# 5VBuck_MP2236_P1.net
KiCad netlist of a schematic drawn in EasyEDA Pro
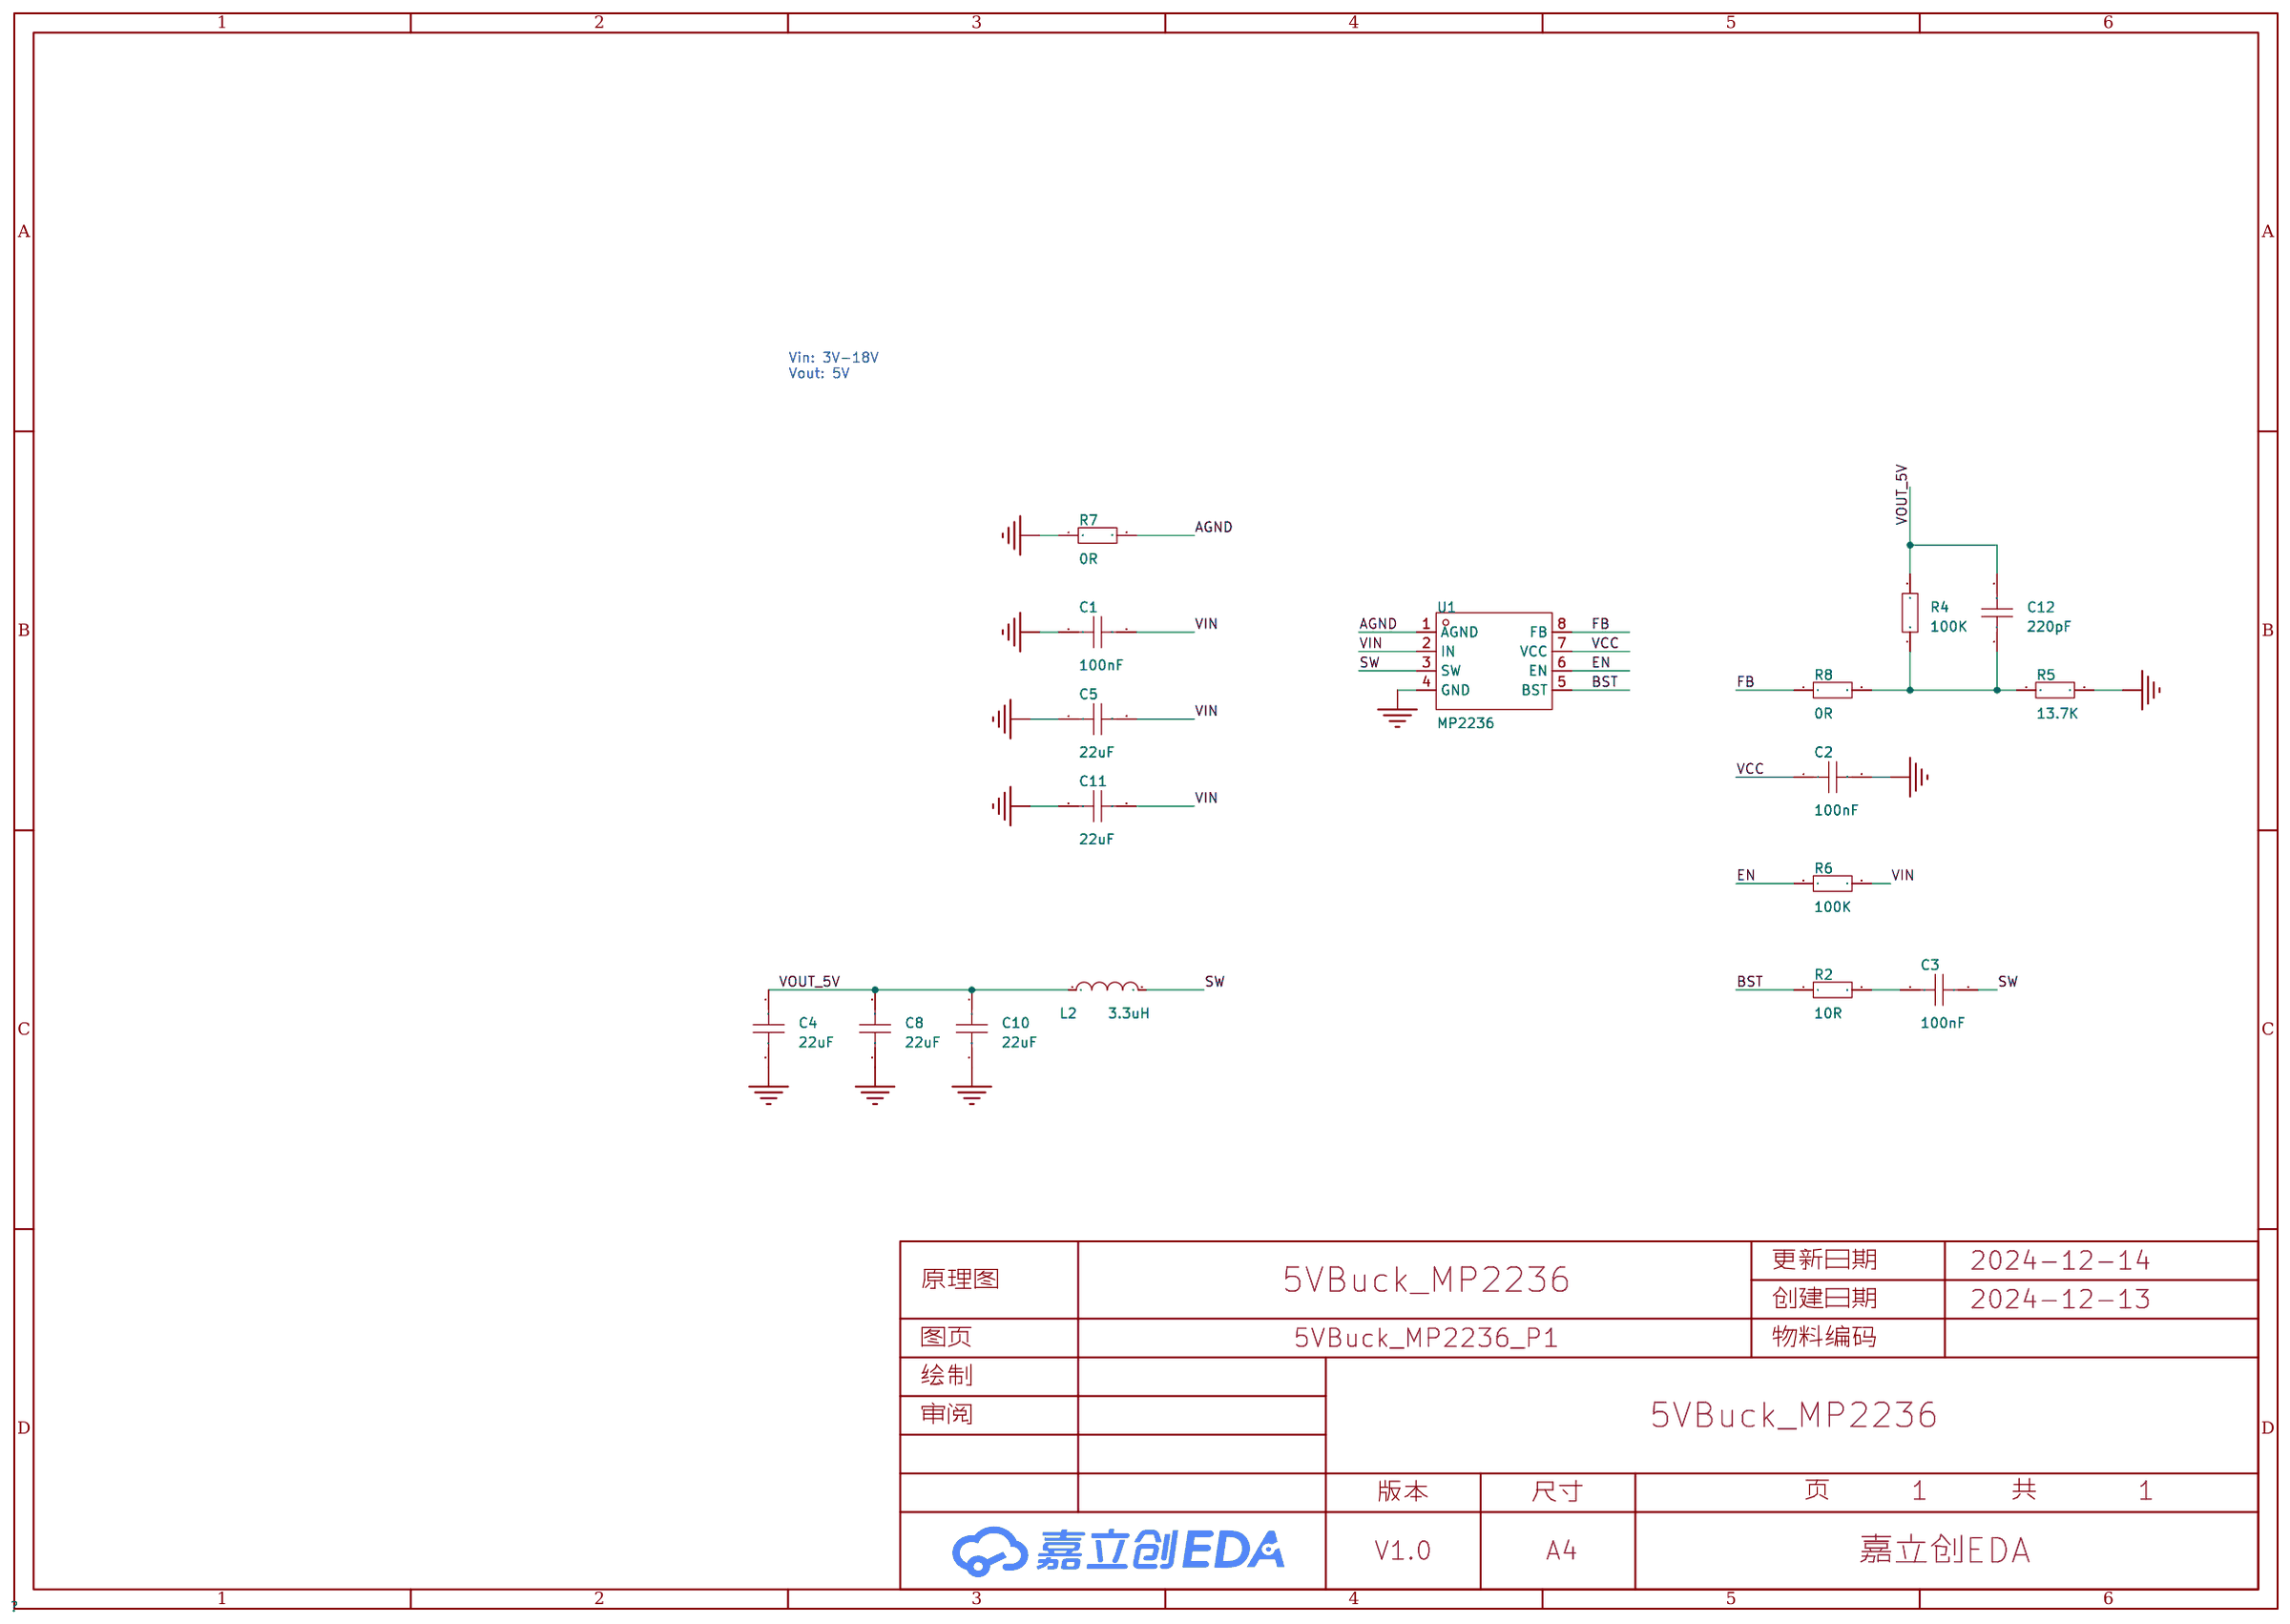
[diagram p0: schematic sheet]

(export (version "E")
  (design (tool "Eeschema 10.0.6"))
  (components
    (comp (ref "C1")
      (value "100nF")
      (footprint "easyedapro:C0805")
      (libsource (lib "easyedapro") (part "CapAcitance"))
    )
    (comp (ref "C2")
      (value "100nF")
      (footprint "easyedapro:C0805")
      (libsource (lib "easyedapro") (part "CapAcitance"))
    )
    (comp (ref "C3")
      (value "100nF")
      (footprint "easyedapro:C0805")
      (libsource (lib "easyedapro") (part "CapAcitance"))
    )
    (comp (ref "C4")
      (value "22uF")
      (footprint "easyedapro:C0805")
      (libsource (lib "easyedapro") (part "CapAcitance"))
    )
    (comp (ref "C5")
      (value "22uF")
      (footprint "easyedapro:C0805")
      (libsource (lib "easyedapro") (part "CapAcitance"))
    )
    (comp (ref "C8")
      (value "22uF")
      (footprint "easyedapro:C0805")
      (libsource (lib "easyedapro") (part "CapAcitance"))
    )
    (comp (ref "C10")
      (value "22uF")
      (footprint "easyedapro:C0805")
      (libsource (lib "easyedapro") (part "CapAcitance"))
    )
    (comp (ref "C11")
      (value "22uF")
      (footprint "easyedapro:C0805")
      (libsource (lib "easyedapro") (part "CapAcitance"))
    )
    (comp (ref "C12")
      (value "220pF")
      (footprint "easyedapro:C0805")
      (libsource (lib "easyedapro") (part "CapAcitance"))
    )
    (comp (ref "L2")
      (value "3.3uH")
      (footprint "easyedapro:IND-SMD_L7.1-W6.6_MJC-0603T")
      (description "电感值:5.6uH;精度:±20%;额定电流:5.5A;饱和电流(Isat):7A;类型:一体成型电感;")
      (fields
        (field (name "Manufacturer Part") "CXP0630-5R6M-AG(5.6uh)")
        (field (name "Manufacturer") "DMBJ(振宝佳)")
      )
      (libsource (lib "easyedapro") (part "CXP0630-5R6M-AG(5.6UH)"))
    )
    (comp (ref "R2") (value "10R") (footprint "easyedapro:R0805") (libsource (lib "easyedapro") (part "电阻")))
    (comp (ref "R4") (value "100K") (footprint "easyedapro:R0805") (libsource (lib "easyedapro") (part "电阻")))
    (comp (ref "R5")
      (value "13.7K")
      (footprint "easyedapro:R0805")
      (libsource (lib "easyedapro") (part "电阻"))
    )
    (comp (ref "R6") (value "100K") (footprint "easyedapro:R0805") (libsource (lib "easyedapro") (part "电阻")))
    (comp (ref "R7") (value "0R") (footprint "easyedapro:R0805") (libsource (lib "easyedapro") (part "电阻")))
    (comp (ref "R8") (value "0R") (footprint "easyedapro:R0805") (libsource (lib "easyedapro") (part "电阻")))
    (comp (ref "U1")
      (value "MP2236")
      (footprint "easyedapro:SOT-23-8_L3.0-W1.7-P0.65-LS2.8-BL")
      (libsource (lib "easyedapro") (part "MP2236"))
    )
  )
  (nets
    (net (code "1") (name "/AGND") (class "Default")
      (node (ref "R7") (pin "2") (pinfunction "2_2") (pintype "input"))
      (node (ref "U1") (pin "1") (pinfunction "AGND_1") (pintype "unspecified"))
    )
    (net (code "2") (name "/BST") (class "Default")
      (node (ref "R2") (pin "1") (pinfunction "1_1") (pintype "input"))
      (node (ref "U1") (pin "5") (pinfunction "BST_5") (pintype "unspecified"))
    )
    (net (code "3") (name "/EN") (class "Default")
      (node (ref "R6") (pin "2") (pinfunction "2_2") (pintype "input"))
      (node (ref "U1") (pin "6") (pinfunction "EN_6") (pintype "unspecified"))
    )
    (net (code "4") (name "/FB") (class "Default")
      (node (ref "R8") (pin "1") (pinfunction "1_1") (pintype "input"))
      (node (ref "U1") (pin "8") (pinfunction "FB_8") (pintype "unspecified"))
    )
    (net (code "5") (name "/SW") (class "Default")
      (node (ref "C3") (pin "2") (pinfunction "2_2") (pintype "input"))
      (node (ref "L2") (pin "2") (pinfunction "2_2") (pintype "unspecified"))
      (node (ref "U1") (pin "3") (pinfunction "SW_3") (pintype "unspecified"))
    )
    (net (code "6") (name "/VCC") (class "Default")
      (node (ref "C2") (pin "1") (pinfunction "1_1") (pintype "input"))
      (node (ref "U1") (pin "7") (pinfunction "VCC_7") (pintype "unspecified"))
    )
    (net (code "7") (name "/VIN") (class "Default")
      (node (ref "C1") (pin "2") (pinfunction "2_2") (pintype "input"))
      (node (ref "C11") (pin "2") (pinfunction "2_2") (pintype "input"))
      (node (ref "C5") (pin "2") (pinfunction "2_2") (pintype "input"))
      (node (ref "R6") (pin "1") (pinfunction "1_1") (pintype "input"))
      (node (ref "U1") (pin "2") (pinfunction "IN_2") (pintype "unspecified"))
    )
    (net (code "8") (name "/VOUT_5V") (class "Default")
      (node (ref "C10") (pin "1") (pinfunction "1_1") (pintype "input"))
      (node (ref "C12") (pin "2") (pinfunction "2_2") (pintype "input"))
      (node (ref "C4") (pin "1") (pinfunction "1_1") (pintype "input"))
      (node (ref "C8") (pin "1") (pinfunction "1_1") (pintype "input"))
      (node (ref "L2") (pin "1") (pinfunction "1_1") (pintype "unspecified"))
      (node (ref "R4") (pin "2") (pinfunction "2_2") (pintype "input"))
    )
    (net (code "9") (name "GND") (class "Default")
      (node (ref "C1") (pin "1") (pinfunction "1_1") (pintype "input"))
      (node (ref "C10") (pin "2") (pinfunction "2_2") (pintype "input"))
      (node (ref "C11") (pin "1") (pinfunction "1_1") (pintype "input"))
      (node (ref "C2") (pin "2") (pinfunction "2_2") (pintype "input"))
      (node (ref "C4") (pin "2") (pinfunction "2_2") (pintype "input"))
      (node (ref "C5") (pin "1") (pinfunction "1_1") (pintype "input"))
      (node (ref "C8") (pin "2") (pinfunction "2_2") (pintype "input"))
      (node (ref "R5") (pin "2") (pinfunction "2_2") (pintype "input"))
      (node (ref "R7") (pin "1") (pinfunction "1_1") (pintype "input"))
      (node (ref "U1") (pin "4") (pinfunction "GND_4") (pintype "unspecified"))
    )
    (net (code "10") (name "Net-(C3-Pad1)") (class "Default")
      (node (ref "C3") (pin "1") (pinfunction "1_1") (pintype "input"))
      (node (ref "R2") (pin "2") (pinfunction "2_2") (pintype "input"))
    )
    (net (code "11") (name "Net-(C12-Pad1)") (class "Default")
      (node (ref "C12") (pin "1") (pinfunction "1_1") (pintype "input"))
      (node (ref "R4") (pin "1") (pinfunction "1_1") (pintype "input"))
      (node (ref "R5") (pin "1") (pinfunction "1_1") (pintype "input"))
      (node (ref "R8") (pin "2") (pinfunction "2_2") (pintype "input"))
    )
  )
)
